# control-zenerbridge.net
KiCad netlist of a schematic drawn in EAGLE
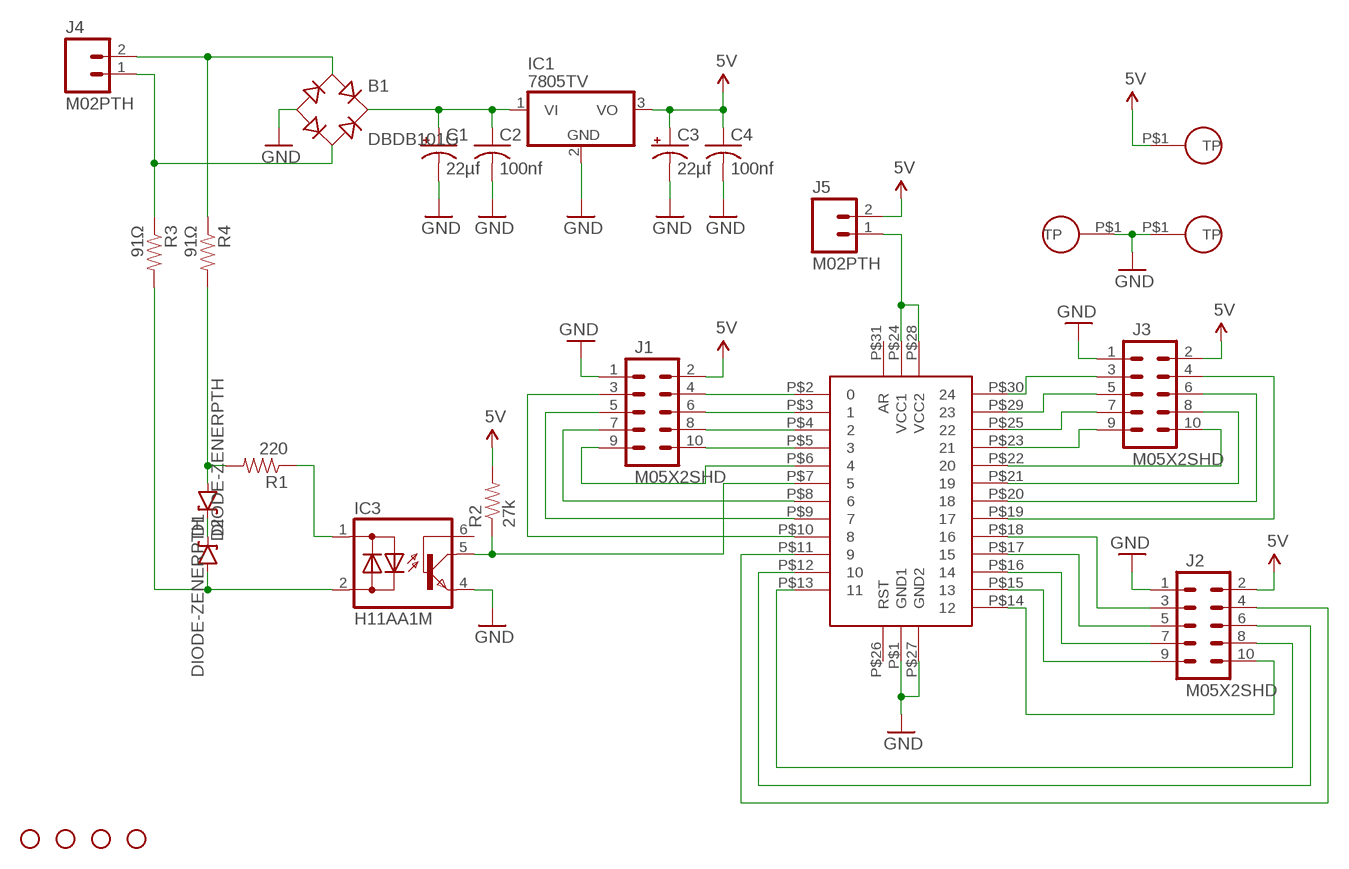
[diagram p0: schematic, sheet 1]

(export (version "E")
  (design (tool "Eeschema 10.0.6"))
  (components
    (comp (ref "B1")
      (value "DBDB101G")
      (footprint "eagle-import:DB")
      (libsource (lib "eagle-import") (part "DB?GDB101"))
    )
    (comp (ref "C1")
      (value "22µf")
      (footprint "eagle-import:E3,5-10")
      (libsource (lib "eagle-import") (part "CPOL-USE3.5-10"))
    )
    (comp (ref "C2")
      (value "100nf")
      (footprint "eagle-import:C025-030X050")
      (libsource (lib "eagle-import") (part "C-US025-030X050"))
    )
    (comp (ref "C3")
      (value "22µf")
      (footprint "eagle-import:E3,5-10")
      (libsource (lib "eagle-import") (part "CPOL-USE3.5-10"))
    )
    (comp (ref "C4")
      (value "100nf")
      (footprint "eagle-import:C025-030X050")
      (libsource (lib "eagle-import") (part "C-US025-030X050"))
    )
    (comp (ref "D1")
      (value "DIODE-ZENERPTH")
      (footprint "eagle-import:DIODE-ZENER")
      (libsource (lib "eagle-import") (part "DIODE-ZENERPTH"))
    )
    (comp (ref "D2")
      (value "DIODE-ZENERPTH")
      (footprint "eagle-import:DIODE-ZENER")
      (libsource (lib "eagle-import") (part "DIODE-ZENERPTH"))
    )
    (comp (ref "IC1")
      (value "7805TV")
      (footprint "eagle-import:TO220V")
      (libsource (lib "eagle-import") (part "78TV05"))
    )
    (comp (ref "IC2")
      (value "TEENSY2")
      (footprint "eagle-import:TEENSY2")
      (libsource (lib "eagle-import") (part "TEENSY2"))
    )
    (comp (ref "IC3")
      (value "H11AA1M")
      (footprint "eagle-import:DIL06")
      (fields (field (name "MF") "Fairchild"))
      (libsource (lib "eagle-import") (part "H11AA1M"))
    )
    (comp (ref "J1")
      (value "M05X2SHD")
      (footprint "eagle-import:2X5-SHROUDED")
      (libsource (lib "eagle-import") (part "M05X2SHD"))
    )
    (comp (ref "J2")
      (value "M05X2SHD")
      (footprint "eagle-import:2X5-SHROUDED")
      (libsource (lib "eagle-import") (part "M05X2SHD"))
    )
    (comp (ref "J3")
      (value "M05X2SHD")
      (footprint "eagle-import:2X5-SHROUDED")
      (libsource (lib "eagle-import") (part "M05X2SHD"))
    )
    (comp (ref "J4")
      (value "M02PTH")
      (footprint "eagle-import:1X02")
      (libsource (lib "eagle-import") (part "M02PTH"))
    )
    (comp (ref "J5")
      (value "M02PTH")
      (footprint "eagle-import:1X02")
      (libsource (lib "eagle-import") (part "M02PTH"))
    )
    (comp (ref "R1")
      (value "220")
      (footprint "eagle-import:AXIAL-0.4")
      (libsource (lib "eagle-import") (part "RESISTORPTH-1/4W"))
    )
    (comp (ref "R2")
      (value "27k")
      (footprint "eagle-import:AXIAL-0.4")
      (libsource (lib "eagle-import") (part "RESISTORPTH-1/4W"))
    )
    (comp (ref "R3")
      (value "91Ω")
      (footprint "eagle-import:AXIAL-0.4")
      (libsource (lib "eagle-import") (part "RESISTORPTH-1/4W"))
    )
    (comp (ref "R4")
      (value "91Ω")
      (footprint "eagle-import:AXIAL-0.4")
      (libsource (lib "eagle-import") (part "RESISTORPTH-1/4W"))
    )
    (comp (ref "STANDOFF1")
      (value "STAND-OFF")
      (footprint "eagle-import:STAND-OFF")
      (libsource (lib "eagle-import") (part "STAND-OFF"))
    )
    (comp (ref "STANDOFF2")
      (value "STAND-OFF")
      (footprint "eagle-import:STAND-OFF")
      (libsource (lib "eagle-import") (part "STAND-OFF"))
    )
    (comp (ref "STANDOFF3")
      (value "STAND-OFF")
      (footprint "eagle-import:STAND-OFF")
      (libsource (lib "eagle-import") (part "STAND-OFF"))
    )
    (comp (ref "STANDOFF4")
      (value "STAND-OFF")
      (footprint "eagle-import:STAND-OFF")
      (libsource (lib "eagle-import") (part "STAND-OFF"))
    )
    (comp (ref "U$3") (value "TP") (footprint "eagle-import:TP") (libsource (lib "eagle-import") (part "TP")))
    (comp (ref "U$8") (value "TP") (footprint "eagle-import:TP") (libsource (lib "eagle-import") (part "TP")))
    (comp (ref "U$9") (value "TP") (footprint "eagle-import:TP") (libsource (lib "eagle-import") (part "TP")))
  )
  (nets
    (net (code "1") (name "5V") (class "Default")
      (node (ref "C3") (pin "+") (pinfunction "+_+") (pintype "passive"))
      (node (ref "C4") (pin "1") (pinfunction "1_1") (pintype "passive"))
      (node (ref "IC1") (pin "3") (pinfunction "VO_3") (pintype "passive"))
      (node (ref "J1") (pin "2") (pinfunction "2_2") (pintype "passive"))
      (node (ref "J2") (pin "2") (pinfunction "2_2") (pintype "passive"))
      (node (ref "J3") (pin "2") (pinfunction "2_2") (pintype "passive"))
      (node (ref "J5") (pin "2") (pinfunction "2_2") (pintype "passive"))
      (node (ref "R2") (pin "P$2") (pinfunction "2_P$2") (pintype "passive"))
      (node (ref "U$8") (pin "P$1") (pinfunction "TP_P$1") (pintype "input"))
    )
    (net (code "2") (name "GND") (class "Default")
      (node (ref "B1") (pin "-") (pinfunction "-_-") (pintype "passive"))
      (node (ref "C1") (pin "-") (pinfunction "-_-") (pintype "passive"))
      (node (ref "C2") (pin "2") (pinfunction "2_2") (pintype "passive"))
      (node (ref "C3") (pin "-") (pinfunction "-_-") (pintype "passive"))
      (node (ref "C4") (pin "2") (pinfunction "2_2") (pintype "passive"))
      (node (ref "IC1") (pin "2") (pinfunction "GND_2") (pintype "passive"))
      (node (ref "IC2") (pin "P$1") (pinfunction "GND1_P$1") (pintype "bidirectional"))
      (node (ref "IC2") (pin "P$27") (pinfunction "GND2_P$27") (pintype "bidirectional"))
      (node (ref "IC3") (pin "4") (pinfunction "E_4") (pintype "passive"))
      (node (ref "J1") (pin "1") (pinfunction "1_1") (pintype "passive"))
      (node (ref "J2") (pin "1") (pinfunction "1_1") (pintype "passive"))
      (node (ref "J3") (pin "1") (pinfunction "1_1") (pintype "passive"))
      (node (ref "U$3") (pin "P$1") (pinfunction "TP_P$1") (pintype "input"))
      (node (ref "U$9") (pin "P$1") (pinfunction "TP_P$1") (pintype "input"))
    )
    (net (code "3") (name "Net-(D1-A)") (class "Default")
      (node (ref "D1") (pin "P$2") (pinfunction "A_P$2") (pintype "passive"))
      (node (ref "IC3") (pin "2") (pinfunction "AC2_2") (pintype "passive"))
      (node (ref "R3") (pin "P$2") (pinfunction "2_P$2") (pintype "passive"))
    )
    (net (code "4") (name "Net-(D1-C)") (class "Default")
      (node (ref "D1") (pin "P$1") (pinfunction "C_P$1") (pintype "passive"))
      (node (ref "D2") (pin "P$1") (pinfunction "C_P$1") (pintype "passive"))
    )
    (net (code "5") (name "Net-(D2-A)") (class "Default")
      (node (ref "D2") (pin "P$2") (pinfunction "A_P$2") (pintype "passive"))
      (node (ref "R1") (pin "P$2") (pinfunction "2_P$2") (pintype "passive"))
      (node (ref "R4") (pin "P$2") (pinfunction "2_P$2") (pintype "passive"))
    )
    (net (code "6") (name "Net-(IC1-VI)") (class "Default")
      (node (ref "B1") (pin "+") (pinfunction "+_+") (pintype "passive"))
      (node (ref "C1") (pin "+") (pinfunction "+_+") (pintype "passive"))
      (node (ref "C2") (pin "1") (pinfunction "1_1") (pintype "passive"))
      (node (ref "IC1") (pin "1") (pinfunction "VI_1") (pintype "input"))
    )
    (net (code "7") (name "Net-(IC2-0)") (class "Default")
      (node (ref "IC2") (pin "P$2") (pinfunction "0_P$2") (pintype "bidirectional"))
      (node (ref "J1") (pin "4") (pinfunction "4_4") (pintype "passive"))
    )
    (net (code "8") (name "Net-(IC2-1)") (class "Default")
      (node (ref "IC2") (pin "P$3") (pinfunction "1_P$3") (pintype "bidirectional"))
      (node (ref "J1") (pin "6") (pinfunction "6_6") (pintype "passive"))
    )
    (net (code "9") (name "Net-(IC2-2)") (class "Default")
      (node (ref "IC2") (pin "P$4") (pinfunction "2_P$4") (pintype "bidirectional"))
      (node (ref "J1") (pin "8") (pinfunction "8_8") (pintype "passive"))
    )
    (net (code "10") (name "Net-(IC2-3)") (class "Default")
      (node (ref "IC2") (pin "P$5") (pinfunction "3_P$5") (pintype "bidirectional"))
      (node (ref "J1") (pin "10") (pinfunction "10_10") (pintype "passive"))
    )
    (net (code "11") (name "Net-(IC2-4)") (class "Default")
      (node (ref "IC2") (pin "P$6") (pinfunction "4_P$6") (pintype "bidirectional"))
      (node (ref "J1") (pin "9") (pinfunction "9_9") (pintype "passive"))
    )
    (net (code "12") (name "Net-(IC2-5)") (class "Default")
      (node (ref "IC2") (pin "P$7") (pinfunction "5_P$7") (pintype "bidirectional"))
      (node (ref "IC3") (pin "5") (pinfunction "C_5") (pintype "passive"))
      (node (ref "R2") (pin "P$1") (pinfunction "1_P$1") (pintype "passive"))
    )
    (net (code "13") (name "Net-(IC2-6)") (class "Default")
      (node (ref "IC2") (pin "P$8") (pinfunction "6_P$8") (pintype "bidirectional"))
      (node (ref "J1") (pin "7") (pinfunction "7_7") (pintype "passive"))
    )
    (net (code "14") (name "Net-(IC2-7)") (class "Default")
      (node (ref "IC2") (pin "P$9") (pinfunction "7_P$9") (pintype "bidirectional"))
      (node (ref "J1") (pin "5") (pinfunction "5_5") (pintype "passive"))
    )
    (net (code "15") (name "Net-(IC2-8)") (class "Default")
      (node (ref "IC2") (pin "P$10") (pinfunction "8_P$10") (pintype "bidirectional"))
      (node (ref "J1") (pin "3") (pinfunction "3_3") (pintype "passive"))
    )
    (net (code "16") (name "Net-(IC2-9)") (class "Default")
      (node (ref "IC2") (pin "P$11") (pinfunction "9_P$11") (pintype "bidirectional"))
      (node (ref "J2") (pin "4") (pinfunction "4_4") (pintype "passive"))
    )
    (net (code "17") (name "Net-(IC2-10)") (class "Default")
      (node (ref "IC2") (pin "P$12") (pinfunction "10_P$12") (pintype "bidirectional"))
      (node (ref "J2") (pin "6") (pinfunction "6_6") (pintype "passive"))
    )
    (net (code "18") (name "Net-(IC2-11)") (class "Default")
      (node (ref "IC2") (pin "P$13") (pinfunction "11_P$13") (pintype "bidirectional"))
      (node (ref "J2") (pin "8") (pinfunction "8_8") (pintype "passive"))
    )
    (net (code "19") (name "Net-(IC2-12)") (class "Default")
      (node (ref "IC2") (pin "P$14") (pinfunction "12_P$14") (pintype "bidirectional"))
      (node (ref "J2") (pin "10") (pinfunction "10_10") (pintype "passive"))
    )
    (net (code "20") (name "Net-(IC2-13)") (class "Default")
      (node (ref "IC2") (pin "P$15") (pinfunction "13_P$15") (pintype "bidirectional"))
      (node (ref "J2") (pin "9") (pinfunction "9_9") (pintype "passive"))
    )
    (net (code "21") (name "Net-(IC2-14)") (class "Default")
      (node (ref "IC2") (pin "P$16") (pinfunction "14_P$16") (pintype "bidirectional"))
      (node (ref "J2") (pin "7") (pinfunction "7_7") (pintype "passive"))
    )
    (net (code "22") (name "Net-(IC2-15)") (class "Default")
      (node (ref "IC2") (pin "P$17") (pinfunction "15_P$17") (pintype "bidirectional"))
      (node (ref "J2") (pin "5") (pinfunction "5_5") (pintype "passive"))
    )
    (net (code "23") (name "Net-(IC2-16)") (class "Default")
      (node (ref "IC2") (pin "P$18") (pinfunction "16_P$18") (pintype "bidirectional"))
      (node (ref "J2") (pin "3") (pinfunction "3_3") (pintype "passive"))
    )
    (net (code "24") (name "Net-(IC2-17)") (class "Default")
      (node (ref "IC2") (pin "P$19") (pinfunction "17_P$19") (pintype "bidirectional"))
      (node (ref "J3") (pin "4") (pinfunction "4_4") (pintype "passive"))
    )
    (net (code "25") (name "Net-(IC2-18)") (class "Default")
      (node (ref "IC2") (pin "P$20") (pinfunction "18_P$20") (pintype "bidirectional"))
      (node (ref "J3") (pin "6") (pinfunction "6_6") (pintype "passive"))
    )
    (net (code "26") (name "Net-(IC2-19)") (class "Default")
      (node (ref "IC2") (pin "P$21") (pinfunction "19_P$21") (pintype "bidirectional"))
      (node (ref "J3") (pin "8") (pinfunction "8_8") (pintype "passive"))
    )
    (net (code "27") (name "Net-(IC2-20)") (class "Default")
      (node (ref "IC2") (pin "P$22") (pinfunction "20_P$22") (pintype "bidirectional"))
      (node (ref "J3") (pin "10") (pinfunction "10_10") (pintype "passive"))
    )
    (net (code "28") (name "Net-(IC2-21)") (class "Default")
      (node (ref "IC2") (pin "P$23") (pinfunction "21_P$23") (pintype "bidirectional"))
      (node (ref "J3") (pin "9") (pinfunction "9_9") (pintype "passive"))
    )
    (net (code "29") (name "Net-(IC2-22)") (class "Default")
      (node (ref "IC2") (pin "P$25") (pinfunction "22_P$25") (pintype "bidirectional"))
      (node (ref "J3") (pin "7") (pinfunction "7_7") (pintype "passive"))
    )
    (net (code "30") (name "Net-(IC2-23)") (class "Default")
      (node (ref "IC2") (pin "P$29") (pinfunction "23_P$29") (pintype "bidirectional"))
      (node (ref "J3") (pin "5") (pinfunction "5_5") (pintype "passive"))
    )
    (net (code "31") (name "Net-(IC2-24)") (class "Default")
      (node (ref "IC2") (pin "P$30") (pinfunction "24_P$30") (pintype "bidirectional"))
      (node (ref "J3") (pin "3") (pinfunction "3_3") (pintype "passive"))
    )
    (net (code "32") (name "Net-(IC2-VCC1)") (class "Default")
      (node (ref "IC2") (pin "P$24") (pinfunction "VCC1_P$24") (pintype "bidirectional"))
      (node (ref "IC2") (pin "P$28") (pinfunction "VCC2_P$28") (pintype "bidirectional"))
      (node (ref "J5") (pin "1") (pinfunction "1_1") (pintype "passive"))
    )
    (net (code "33") (name "Net-(IC3-AC1)") (class "Default")
      (node (ref "IC3") (pin "1") (pinfunction "AC1_1") (pintype "passive"))
      (node (ref "R1") (pin "P$1") (pinfunction "1_P$1") (pintype "passive"))
    )
    (net (code "34") (name "Net-(R3-1)") (class "Default")
      (node (ref "B1") (pin "AC2") (pinfunction "AC2_AC2") (pintype "passive"))
      (node (ref "J4") (pin "1") (pinfunction "1_1") (pintype "passive"))
      (node (ref "R3") (pin "P$1") (pinfunction "1_P$1") (pintype "passive"))
    )
    (net (code "35") (name "Net-(R4-1)") (class "Default")
      (node (ref "B1") (pin "AC1") (pinfunction "AC1_AC1") (pintype "passive"))
      (node (ref "J4") (pin "2") (pinfunction "2_2") (pintype "passive"))
      (node (ref "R4") (pin "P$1") (pinfunction "1_P$1") (pintype "passive"))
    )
    (net (code "36") (name "unconnected-(IC2-AR-PadP$31)") (class "Default")
      (node (ref "IC2") (pin "P$31") (pinfunction "AR_P$31") (pintype "bidirectional"))
    )
    (net (code "37") (name "unconnected-(IC2-RST-PadP$26)") (class "Default")
      (node (ref "IC2") (pin "P$26") (pinfunction "RST_P$26") (pintype "bidirectional"))
    )
    (net (code "38") (name "unconnected-(IC3-B-Pad6)") (class "Default")
      (node (ref "IC3") (pin "6") (pinfunction "B_6") (pintype "passive"))
    )
  )
)
